# BEP2_rev1_multiCB.net
KiCad netlist of a schematic drawn in EAGLE
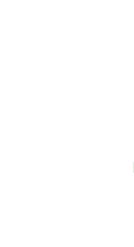
[diagram p0: schematic, sheet 1, part 1 of 2]
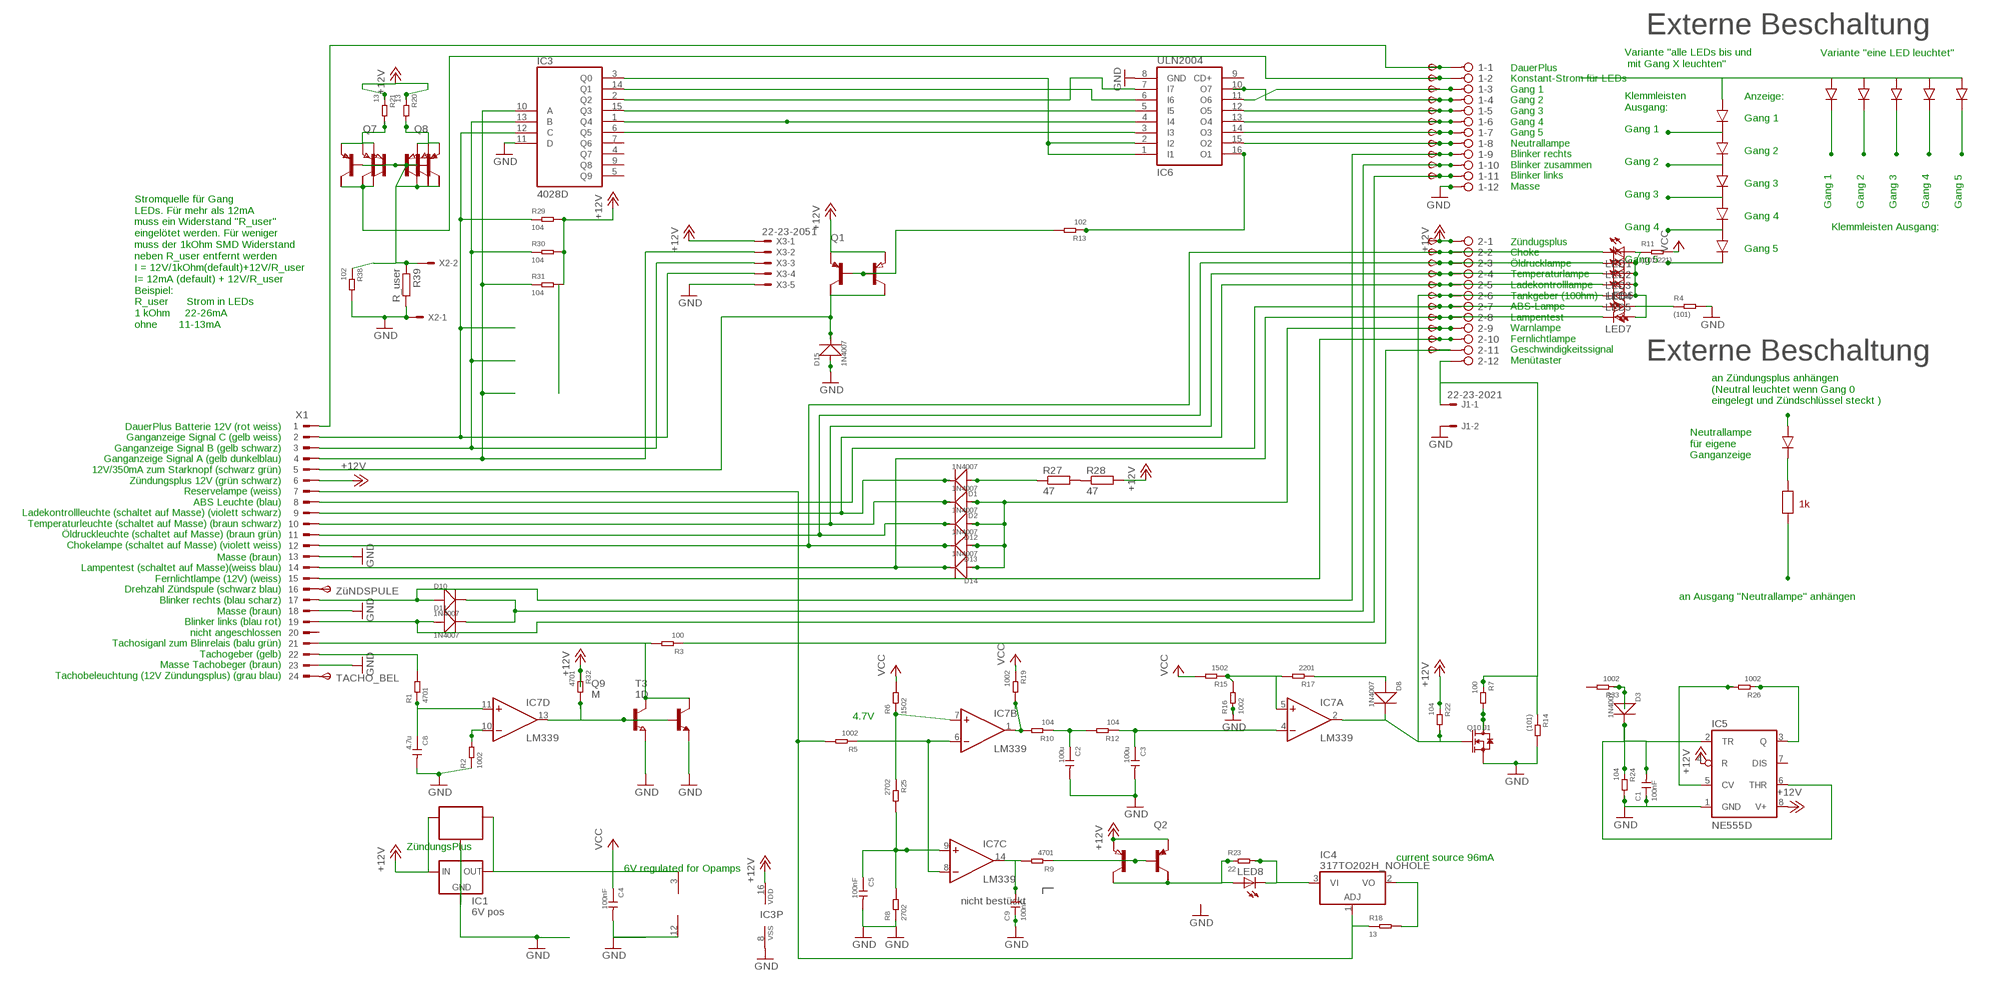
[diagram p1: schematic, sheet 1, part 2 of 2]

(export (version "E")
  (design (tool "Eeschema 10.0.6"))
  (components
    (comp (ref "1")
      (value "2081-1132")
      (footprint "eagle-import:12-PIN")
      (libsource (lib "eagle-import") (part "2081-1132"))
    )
    (comp (ref "2")
      (value "2081-1132")
      (footprint "eagle-import:12-PIN")
      (libsource (lib "eagle-import") (part "2081-1132"))
    )
    (comp (ref "C1")
      (value "100nF")
      (footprint "eagle-import:C0805")
      (fields (field (name "MPN") "CC0805KRX7R9BB104"))
      (libsource (lib "eagle-import") (part "CERAMIC-100NF-50V-10%-X7R(0805)"))
    )
    (comp (ref "C2")
      (value "100u")
      (footprint "eagle-import:C1206")
      (fields (field (name "MPN") "GRM31CR60J107ME39L"))
      (libsource (lib "eagle-import") (part "CERAMIC-100UF-6.3V-20%-X5R(1206)"))
    )
    (comp (ref "C3")
      (value "100u")
      (footprint "eagle-import:C1206")
      (fields (field (name "MPN") "GRM31CR60J107ME39L"))
      (libsource (lib "eagle-import") (part "CERAMIC-100UF-6.3V-20%-X5R(1206)"))
    )
    (comp (ref "C4")
      (value "100nF")
      (footprint "eagle-import:C0805")
      (fields (field (name "MPN") "CC0805KRX7R9BB104"))
      (libsource (lib "eagle-import") (part "CERAMIC-100NF-50V-10%-X7R(0805)"))
    )
    (comp (ref "C5")
      (value "100nF")
      (footprint "eagle-import:C0805")
      (fields (field (name "MPN") "CC0805KRX7R9BB104"))
      (libsource (lib "eagle-import") (part "CERAMIC-100NF-50V-10%-X7R(0805)"))
    )
    (comp (ref "C8")
      (value "4.7u")
      (footprint "eagle-import:C0805")
      (fields (field (name "MPN") "CC0805KKX5R8BB475"))
      (libsource (lib "eagle-import") (part "CERAMIC-4.7UF-25V-10%-X5R(0805)"))
    )
    (comp (ref "C9")
      (value "100nF")
      (footprint "eagle-import:C0805")
      (fields (field (name "MPN") "CC0805KRX7R9BB104"))
      (libsource (lib "eagle-import") (part "CERAMIC-100NF-50V-10%-X7R(0805)"))
    )
    (comp (ref "D1")
      (value "1N4007")
      (footprint "eagle-import:DO-214AC")
      (libsource (lib "eagle-import") (part "DIODE-GEN-PURPOSE-1KV-1A(DO-214AC)"))
    )
    (comp (ref "D2")
      (value "1N4007")
      (footprint "eagle-import:DO-214AC")
      (libsource (lib "eagle-import") (part "DIODE-GEN-PURPOSE-1KV-1A(DO-214AC)"))
    )
    (comp (ref "D3")
      (value "1N4007")
      (footprint "eagle-import:DO-214AC")
      (libsource (lib "eagle-import") (part "DIODE-GEN-PURPOSE-1KV-1A(DO-214AC)"))
    )
    (comp (ref "D8")
      (value "1N4007")
      (footprint "eagle-import:DO-214AC")
      (libsource (lib "eagle-import") (part "Seeed-Diode-2016_DIODE-GEN-PURPOSE-1KV-1A(DO-214AC)"))
    )
    (comp (ref "D10")
      (value "1N4007")
      (footprint "eagle-import:DO-214AC")
      (libsource (lib "eagle-import") (part "DIODE-GEN-PURPOSE-1KV-1A(DO-214AC)"))
    )
    (comp (ref "D11")
      (value "1N4007")
      (footprint "eagle-import:DO-214AC")
      (libsource (lib "eagle-import") (part "DIODE-GEN-PURPOSE-1KV-1A(DO-214AC)"))
    )
    (comp (ref "D12")
      (value "1N4007")
      (footprint "eagle-import:DO-214AC")
      (libsource (lib "eagle-import") (part "DIODE-GEN-PURPOSE-1KV-1A(DO-214AC)"))
    )
    (comp (ref "D13")
      (value "1N4007")
      (footprint "eagle-import:DO-214AC")
      (libsource (lib "eagle-import") (part "DIODE-GEN-PURPOSE-1KV-1A(DO-214AC)"))
    )
    (comp (ref "D14")
      (value "1N4007")
      (footprint "eagle-import:DO-214AC")
      (libsource (lib "eagle-import") (part "DIODE-GEN-PURPOSE-1KV-1A(DO-214AC)"))
    )
    (comp (ref "D15")
      (value "1N4007")
      (footprint "eagle-import:DO-214AC")
      (libsource (lib "eagle-import") (part "DIODE-GEN-PURPOSE-1KV-1A(DO-214AC)"))
    )
    (comp (ref "IC1")
      (value "6V pos")
      (footprint "eagle-import:78LXX")
      (libsource (lib "eagle-import") (part "v-reg_78LXX"))
    )
    (comp (ref "IC2")
      (value "78LXX-SOT89")
      (footprint "eagle-import:SOT89")
      (libsource (lib "eagle-import") (part "78LXX-SOT89"))
    )
    (comp (ref "IC3")
      (value "4028D")
      (footprint "eagle-import:SO16")
      (libsource (lib "eagle-import") (part "4028D"))
    )
    (comp (ref "IC4")
      (value "317TO202H_NOHOLE")
      (footprint "eagle-import:TO220H_NOHOLE")
      (libsource (lib "eagle-import") (part "317TO202H_NOHOLE"))
    )
    (comp (ref "IC5")
      (value "NE555D")
      (footprint "eagle-import:SO08")
      (libsource (lib "eagle-import") (part "555DNE"))
    )
    (comp (ref "IC6")
      (value "ULN2004")
      (footprint "eagle-import:SO16")
      (libsource (lib "eagle-import") (part "ULN2004AD"))
    )
    (comp (ref "IC7")
      (value "LM339")
      (footprint "eagle-import:SO14")
      (libsource (lib "eagle-import") (part "LM339D"))
    )
    (comp (ref "J1")
      (value "22-23-2021")
      (footprint "eagle-import:22-23-2021")
      (fields (field (name "MF") "MOLEX"))
      (libsource (lib "eagle-import") (part "22-23-2021"))
    )
    (comp (ref "LED1")
      (value "LEDLD260")
      (footprint "eagle-import:LD260")
      (libsource (lib "eagle-import") (part "LEDLD260"))
    )
    (comp (ref "LED2")
      (value "LEDLD260")
      (footprint "eagle-import:LD260")
      (libsource (lib "eagle-import") (part "LEDLD260"))
    )
    (comp (ref "LED3")
      (value "LEDLD260")
      (footprint "eagle-import:LD260")
      (libsource (lib "eagle-import") (part "LEDLD260"))
    )
    (comp (ref "LED4")
      (value "LEDLD260")
      (footprint "eagle-import:LD260")
      (libsource (lib "eagle-import") (part "LEDLD260"))
    )
    (comp (ref "LED5")
      (value "LEDLD260")
      (footprint "eagle-import:LD260")
      (libsource (lib "eagle-import") (part "LEDLD260"))
    )
    (comp (ref "LED6")
      (value "LEDLD260")
      (footprint "eagle-import:LD260")
      (libsource (lib "eagle-import") (part "LEDLD260"))
    )
    (comp (ref "LED7")
      (value "LEDLD260")
      (footprint "eagle-import:LD260")
      (libsource (lib "eagle-import") (part "LEDLD260"))
    )
    (comp (ref "LED8")
      (value "LEDLD260")
      (footprint "eagle-import:LD260")
      (libsource (lib "eagle-import") (part "LEDLD260"))
    )
    (comp (ref "Q1")
      (value "PNP-TRANSISTOR_SOT89")
      (footprint "eagle-import:SOT89")
      (libsource (lib "eagle-import") (part "PNP-TRANSISTOR_SOT89"))
    )
    (comp (ref "Q2")
      (value "PNP-TRANSISTOR_SOT89")
      (footprint "eagle-import:SOT89")
      (libsource (lib "eagle-import") (part "PNP-TRANSISTOR_SOT89"))
    )
    (comp (ref "Q3")
      (value "AH-16")
      (footprint "eagle-import:SOT223")
      (libsource (lib "eagle-import") (part "BCP53T1"))
    )
    (comp (ref "Q4")
      (value "AH-16")
      (footprint "eagle-import:SOT223")
      (libsource (lib "eagle-import") (part "BCP53T1"))
    )
    (comp (ref "Q5")
      (value "(AH-16)")
      (footprint "eagle-import:SOT223")
      (libsource (lib "eagle-import") (part "BCP53T1"))
    )
    (comp (ref "Q6")
      (value "(AH-16)")
      (footprint "eagle-import:SOT223")
      (libsource (lib "eagle-import") (part "BCP53T1"))
    )
    (comp (ref "Q7")
      (value "PNP-TRANSISTOR_SOT89")
      (footprint "eagle-import:SOT89")
      (libsource (lib "eagle-import") (part "PNP-TRANSISTOR_SOT89"))
    )
    (comp (ref "Q8")
      (value "PNP-TRANSISTOR_SOT89")
      (footprint "eagle-import:SOT89")
      (libsource (lib "eagle-import") (part "PNP-TRANSISTOR_SOT89"))
    )
    (comp (ref "Q9")
      (value "M")
      (footprint "eagle-import:SOT89")
      (libsource (lib "eagle-import") (part "NPN-TRANSISTOR_SOT89"))
    )
    (comp (ref "Q10")
      (value "J1")
      (footprint "eagle-import:SOT-23")
      (fields (field (name "MPN") "BSS138W-7-F"))
      (libsource (lib "eagle-import") (part "SMD-MOSFET-N-CH-50V-200MA-BSS138W-7-F(SOT-23)"))
    )
    (comp (ref "R1")
      (value "4701")
      (footprint "eagle-import:R0805")
      (fields (field (name "MPN") "RC0805JR-074K7L"))
      (libsource (lib "eagle-import") (part "SMD-RES-4.7K-5%-1/8W(0805)"))
    )
    (comp (ref "R2")
      (value "1002")
      (footprint "eagle-import:R0805")
      (fields (field (name "MPN") "RC0805FR-0710KL"))
      (libsource (lib "eagle-import") (part "SMD-RES-10K-1%-1/8W(0805)"))
    )
    (comp (ref "R3")
      (value "100")
      (footprint "eagle-import:R0805")
      (fields (field (name "MPN") "RC0805JR-07220RL"))
      (libsource (lib "eagle-import") (part "SMD-RES-220R-5%-1/8W(0805)"))
    )
    (comp (ref "R4")
      (value "(101)")
      (footprint "eagle-import:R0805")
      (fields (field (name "MPN") "RC0805JR-07100RL"))
      (libsource (lib "eagle-import") (part "SMD-RES-100R-5%-1/8W(0805)"))
    )
    (comp (ref "R5")
      (value "1002")
      (footprint "eagle-import:R0805")
      (fields (field (name "MPN") "RC0805FR-0710KL"))
      (libsource (lib "eagle-import") (part "SMD-RES-10K-1%-1/8W(0805)"))
    )
    (comp (ref "R6")
      (value "1502")
      (footprint "eagle-import:R0805")
      (fields (field (name "MPN") "RC0805FR-0710KL"))
      (libsource (lib "eagle-import") (part "SMD-RES-10K-1%-1/8W(0805)"))
    )
    (comp (ref "R7")
      (value "100")
      (footprint "eagle-import:R0805")
      (fields (field (name "MPN") "RC0805JR-072K2L"))
      (libsource (lib "eagle-import") (part "SMD-RES-2.2K-5%-1/8W(0805)"))
    )
    (comp (ref "R8")
      (value "2702")
      (footprint "eagle-import:R0805")
      (fields (field (name "MPN") "RC0805JR-074K7L"))
      (libsource (lib "eagle-import") (part "SMD-RES-4.7K-5%-1/8W(0805)"))
    )
    (comp (ref "R9")
      (value "4701")
      (footprint "eagle-import:R0805")
      (fields (field (name "MPN") "RC0805JR-074K7L"))
      (libsource (lib "eagle-import") (part "SMD-RES-4.7K-5%-1/8W(0805)"))
    )
    (comp (ref "R10")
      (value "104")
      (footprint "eagle-import:R0805")
      (fields (field (name "MPN") "RC0805FR-0710KL"))
      (libsource (lib "eagle-import") (part "SMD-RES-10K-1%-1/8W(0805)"))
    )
    (comp (ref "R11")
      (value "(101/221)")
      (footprint "eagle-import:R0805")
      (fields (field (name "MPN") "RC0805JR-07100RL"))
      (libsource (lib "eagle-import") (part "SMD-RES-100R-5%-1/8W(0805)"))
    )
    (comp (ref "R12")
      (value "104")
      (footprint "eagle-import:R0805")
      (fields (field (name "MPN") "RC0805FR-0710KL"))
      (libsource (lib "eagle-import") (part "SMD-RES-10K-1%-1/8W(0805)"))
    )
    (comp (ref "R13")
      (value "102")
      (footprint "eagle-import:R0805")
      (fields (field (name "MPN") "RC0805JR-071KL"))
      (libsource (lib "eagle-import") (part "SMD-RES-1K-5%-1/8W(0805)"))
    )
    (comp (ref "R14")
      (value "(101)")
      (footprint "eagle-import:R0805")
      (fields (field (name "MPN") "RC0805JR-072K2L"))
      (libsource (lib "eagle-import") (part "SMD-RES-2.2K-5%-1/8W(0805)"))
    )
    (comp (ref "R15")
      (value "1502")
      (footprint "eagle-import:R0805")
      (fields (field (name "MPN") "RC0805FR-0710KL"))
      (libsource (lib "eagle-import") (part "SMD-RES-10K-1%-1/8W(0805)"))
    )
    (comp (ref "R16")
      (value "1002")
      (footprint "eagle-import:R0805")
      (fields (field (name "MPN") "RC0805FR-0710KL"))
      (libsource (lib "eagle-import") (part "SMD-RES-10K-1%-1/8W(0805)"))
    )
    (comp (ref "R17")
      (value "2201")
      (footprint "eagle-import:R0805")
      (fields (field (name "MPN") "RC0805JR-072K2L"))
      (libsource (lib "eagle-import") (part "SMD-RES-2.2K-5%-1/8W(0805)"))
    )
    (comp (ref "R18")
      (value "13")
      (footprint "eagle-import:R1206")
      (fields (field (name "MPN") "RC1206JR-0713RL"))
      (libsource (lib "eagle-import") (part "SMD-RES-13R-5%-1/4W(1206)"))
    )
    (comp (ref "R19")
      (value "1002")
      (footprint "eagle-import:R0805")
      (fields (field (name "MPN") "RC0805FR-0710KL"))
      (libsource (lib "eagle-import") (part "SMD-RES-10K-1%-1/8W(0805)"))
    )
    (comp (ref "R20")
      (value "13")
      (footprint "eagle-import:R1206")
      (fields (field (name "MPN") "RC1206JR-0713RL"))
      (libsource (lib "eagle-import") (part "SMD-RES-13R-5%-1/4W(1206)"))
    )
    (comp (ref "R21")
      (value "13")
      (footprint "eagle-import:R1206")
      (fields (field (name "MPN") "RC1206JR-0713RL"))
      (libsource (lib "eagle-import") (part "SMD-RES-13R-5%-1/4W(1206)"))
    )
    (comp (ref "R22")
      (value "104")
      (footprint "eagle-import:R0805")
      (fields (field (name "MPN") "RC0805FR-0710KL"))
      (libsource (lib "eagle-import") (part "SMD-RES-10K-1%-1/8W(0805)"))
    )
    (comp (ref "R23")
      (value "22")
      (footprint "eagle-import:R1206")
      (fields (field (name "MPN") "RC1206JR-0713RL"))
      (libsource (lib "eagle-import") (part "SMD-RES-13R-5%-1/4W(1206)"))
    )
    (comp (ref "R24")
      (value "104")
      (footprint "eagle-import:R0805")
      (fields (field (name "MPN") "RC0805FR-0710KL"))
      (libsource (lib "eagle-import") (part "SMD-RES-10K-1%-1/8W(0805)"))
    )
    (comp (ref "R25")
      (value "2702")
      (footprint "eagle-import:R0805")
      (fields (field (name "MPN") "RC0805JR-074K7L"))
      (libsource (lib "eagle-import") (part "SMD-RES-4.7K-5%-1/8W(0805)"))
    )
    (comp (ref "R26")
      (value "1002")
      (footprint "eagle-import:R0805")
      (fields (field (name "MPN") "RC0805FR-0710KL"))
      (libsource (lib "eagle-import") (part "SMD-RES-10K-1%-1/8W(0805)"))
    )
    (comp (ref "R27")
      (value "47")
      (footprint "eagle-import:V235_17_1MM")
      (libsource (lib "eagle-import") (part "R-EU_V235/17_1MM"))
    )
    (comp (ref "R28")
      (value "47")
      (footprint "eagle-import:V235_17_1MM")
      (libsource (lib "eagle-import") (part "R-EU_V235/17_1MM"))
    )
    (comp (ref "R29")
      (value "104")
      (footprint "eagle-import:R0805")
      (fields (field (name "MPN") "RC0805FR-0710KL"))
      (libsource (lib "eagle-import") (part "SMD-RES-10K-1%-1/8W(0805)"))
    )
    (comp (ref "R30")
      (value "104")
      (footprint "eagle-import:R0805")
      (fields (field (name "MPN") "RC0805FR-0710KL"))
      (libsource (lib "eagle-import") (part "SMD-RES-10K-1%-1/8W(0805)"))
    )
    (comp (ref "R31")
      (value "104")
      (footprint "eagle-import:R0805")
      (fields (field (name "MPN") "RC0805FR-0710KL"))
      (libsource (lib "eagle-import") (part "SMD-RES-10K-1%-1/8W(0805)"))
    )
    (comp (ref "R32")
      (value "4701")
      (footprint "eagle-import:R0805")
      (fields (field (name "MPN") "RC0805JR-074K7L"))
      (libsource (lib "eagle-import") (part "SMD-RES-4.7K-5%-1/8W(0805)"))
    )
    (comp (ref "R33")
      (value "1002")
      (footprint "eagle-import:R0805")
      (fields (field (name "MPN") "RC0805FR-0710KL"))
      (libsource (lib "eagle-import") (part "SMD-RES-10K-1%-1/8W(0805)"))
    )
    (comp (ref "R38")
      (value "102")
      (footprint "eagle-import:R0805")
      (fields (field (name "MPN") "RC0805JR-071KL"))
      (libsource (lib "eagle-import") (part "SMD-RES-1K-5%-1/8W(0805)"))
    )
    (comp (ref "R39")
      (value "R_user")
      (footprint "eagle-import:R0805")
      (libsource (lib "eagle-import") (part "R-EU_R0805"))
    )
    (comp (ref "T1")
      (value "PNP2SM8")
      (footprint "eagle-import:SM8")
      (libsource (lib "eagle-import") (part "PNP2SM8"))
    )
    (comp (ref "T3")
      (value "1D")
      (footprint "eagle-import:SOT23-BEC")
      (libsource (lib "eagle-import") (part "-NPN-SOT23-BECMMBTA42LT1"))
    )
    (comp (ref "TACHO_BEL")
      (value "TPSP1_1MM")
      (footprint "eagle-import:P1_1.0MM")
      (libsource (lib "eagle-import") (part "TPSP1_1MM"))
    )
    (comp (ref "TP1")
      (value "TPSB1.8")
      (footprint "eagle-import:B1.8")
      (libsource (lib "eagle-import") (part "TPSB1.8"))
    )
    (comp (ref "TP2")
      (value "TPSB1.8")
      (footprint "eagle-import:B1.8")
      (libsource (lib "eagle-import") (part "TPSB1.8"))
    )
    (comp (ref "TP3")
      (value "TPSB1.8")
      (footprint "eagle-import:B1.8")
      (libsource (lib "eagle-import") (part "TPSB1.8"))
    )
    (comp (ref "TP4")
      (value "TPSB1.8")
      (footprint "eagle-import:B1.8")
      (libsource (lib "eagle-import") (part "TPSB1.8"))
    )
    (comp (ref "TP5")
      (value "TPSB1.8")
      (footprint "eagle-import:B1.8")
      (libsource (lib "eagle-import") (part "TPSB1.8"))
    )
    (comp (ref "TP6")
      (value "TPSB1.8")
      (footprint "eagle-import:B1.8")
      (libsource (lib "eagle-import") (part "TPSB1.8"))
    )
    (comp (ref "TP7")
      (value "TPSB1.8")
      (footprint "eagle-import:B1.8")
      (libsource (lib "eagle-import") (part "TPSB1.8"))
    )
    (comp (ref "TP8")
      (value "TPSB1.8")
      (footprint "eagle-import:B1.8")
      (libsource (lib "eagle-import") (part "TPSB1.8"))
    )
    (comp (ref "TP9")
      (value "TPSB1.8")
      (footprint "eagle-import:B1.8")
      (libsource (lib "eagle-import") (part "TPSB1.8"))
    )
    (comp (ref "TP10")
      (value "TPSB1.8")
      (footprint "eagle-import:B1.8")
      (libsource (lib "eagle-import") (part "TPSB1.8"))
    )
    (comp (ref "TP11")
      (value "TPSB1.8")
      (footprint "eagle-import:B1.8")
      (libsource (lib "eagle-import") (part "TPSB1.8"))
    )
    (comp (ref "TP12")
      (value "TPSB1.8")
      (footprint "eagle-import:B1.8")
      (libsource (lib "eagle-import") (part "TPSB1.8"))
    )
    (comp (ref "TP16")
      (value "TPSB1.8")
      (footprint "eagle-import:B1.8")
      (libsource (lib "eagle-import") (part "TPSB1.8"))
    )
    (comp (ref "TP17")
      (value "TPSB1.8")
      (footprint "eagle-import:B1.8")
      (libsource (lib "eagle-import") (part "TPSB1.8"))
    )
    (comp (ref "TP18")
      (value "TPSB1.8")
      (footprint "eagle-import:B1.8")
      (libsource (lib "eagle-import") (part "TPSB1.8"))
    )
    (comp (ref "TP19")
      (value "TPSB1.8")
      (footprint "eagle-import:B1.8")
      (libsource (lib "eagle-import") (part "TPSB1.8"))
    )
    (comp (ref "TP21")
      (value "TPSB1.8")
      (footprint "eagle-import:B1.8")
      (libsource (lib "eagle-import") (part "TPSB1.8"))
    )
    (comp (ref "TP22")
      (value "TPSB1.8")
      (footprint "eagle-import:B1.8")
      (libsource (lib "eagle-import") (part "TPSB1.8"))
    )
    (comp (ref "TP23")
      (value "TPSB1.8")
      (footprint "eagle-import:B1.8")
      (libsource (lib "eagle-import") (part "TPSB1.8"))
    )
    (comp (ref "TP24")
      (value "TPSB1,27")
      (footprint "eagle-import:B1,27")
      (libsource (lib "eagle-import") (part "TPSB1,27"))
    )
    (comp (ref "TP25")
      (value "TPSB1.8")
      (footprint "eagle-import:B1.8")
      (libsource (lib "eagle-import") (part "TPSB1.8"))
    )
    (comp (ref "TP26")
      (value "TPSB1.8")
      (footprint "eagle-import:B1.8")
      (libsource (lib "eagle-import") (part "TPSB1.8"))
    )
    (comp (ref "X1")
      (value "CON_BMWV2")
      (footprint "eagle-import:24-PIN_V2")
      (libsource (lib "eagle-import") (part "CON_BMWV2"))
    )
    (comp (ref "X2")
      (value "22-23-2021")
      (footprint "eagle-import:22-23-2021")
      (fields (field (name "MF") "MOLEX"))
      (libsource (lib "eagle-import") (part "22-23-2021"))
    )
    (comp (ref "X3")
      (value "22-23-2051")
      (footprint "eagle-import:22-23-2051")
      (fields (field (name "MF") "MOLEX"))
      (libsource (lib "eagle-import") (part "22-23-2051"))
    )
    (comp (ref "ZüNDSPULE")
      (value "TPSP1_1MM")
      (footprint "eagle-import:P1_1.0MM")
      (libsource (lib "eagle-import") (part "TPSP1_1MM"))
    )
  )
  (nets
    (net (code "1") (name "+12V") (class "Default")
      (node (ref "2") (pin "1") (pinfunction "KL_1") (pintype "passive"))
      (node (ref "IC1") (pin "IN") (pinfunction "IN_IN") (pintype "input"))
      (node (ref "IC2") (pin "3") (pinfunction "IN_3") (pintype "input"))
      (node (ref "IC3") (pin "16") (pinfunction "VDD_16") (pintype "power_in"))
      (node (ref "IC5") (pin "4") (pinfunction "R_4") (pintype "input"))
      (node (ref "IC5") (pin "8") (pinfunction "V+_8") (pintype "power_in"))
      (node (ref "Q1") (pin "3") (pinfunction "E_3") (pintype "passive"))
      (node (ref "Q2") (pin "3") (pinfunction "E_3") (pintype "passive"))
      (node (ref "Q3") (pin "3") (pinfunction "E_3") (pintype "passive"))
      (node (ref "Q4") (pin "3") (pinfunction "E_3") (pintype "passive"))
      (node (ref "R20") (pin "1") (pinfunction "1_1") (pintype "passive"))
      (node (ref "R21") (pin "1") (pinfunction "1_1") (pintype "passive"))
      (node (ref "R22") (pin "1") (pinfunction "1_1") (pintype "passive"))
      (node (ref "R28") (pin "2") (pinfunction "2_2") (pintype "passive"))
      (node (ref "R29") (pin "2") (pinfunction "2_2") (pintype "passive"))
      (node (ref "R30") (pin "2") (pinfunction "2_2") (pintype "passive"))
      (node (ref "R31") (pin "2") (pinfunction "2_2") (pintype "passive"))
      (node (ref "R32") (pin "1") (pinfunction "1_1") (pintype "passive"))
      (node (ref "TP12") (pin "TP") (pinfunction "PP_TP") (pintype "input"))
      (node (ref "X1") (pin "6") (pinfunction "6_6") (pintype "passive"))
      (node (ref "X3") (pin "1") (pinfunction "S_1") (pintype "passive"))
    )
    (net (code "2") (name "GND") (class "Default")
      (node (ref "1") (pin "12") (pinfunction "KL_12") (pintype "passive"))
      (node (ref "C1") (pin "1") (pinfunction "1_1") (pintype "passive"))
      (node (ref "C2") (pin "2") (pinfunction "2_2") (pintype "passive"))
      (node (ref "C3") (pin "2") (pinfunction "2_2") (pintype "passive"))
      (node (ref "C4") (pin "2") (pinfunction "2_2") (pintype "passive"))
      (node (ref "C5") (pin "2") (pinfunction "2_2") (pintype "passive"))
      (node (ref "C8") (pin "2") (pinfunction "2_2") (pintype "passive"))
      (node (ref "C9") (pin "1") (pinfunction "1_1") (pintype "passive"))
      (node (ref "D15") (pin "1") (pinfunction "+_1") (pintype "passive"))
      (node (ref "IC1") (pin "GND") (pinfunction "GND_GND") (pintype "input"))
      (node (ref "IC2") (pin "2") (pinfunction "GND_2") (pintype "input"))
      (node (ref "IC2") (pin "4") (pinfunction "GND_4") (pintype "input"))
      (node (ref "IC3") (pin "11") (pinfunction "D_11") (pintype "input"))
      (node (ref "IC3") (pin "8") (pinfunction "VSS_8") (pintype "power_in"))
      (node (ref "IC5") (pin "1") (pinfunction "GND_1") (pintype "power_in"))
      (node (ref "IC6") (pin "8") (pinfunction "GND_8") (pintype "power_in"))
      (node (ref "IC7") (pin "12") (pinfunction "GND_12") (pintype "power_in"))
      (node (ref "J1") (pin "2") (pinfunction "S_2") (pintype "passive"))
      (node (ref "Q10") (pin "2") (pinfunction "S_2") (pintype "passive"))
      (node (ref "Q9") (pin "3") (pinfunction "E_3") (pintype "passive"))
      (node (ref "R14") (pin "2") (pinfunction "2_2") (pintype "passive"))
      (node (ref "R16") (pin "1") (pinfunction "1_1") (pintype "passive"))
      (node (ref "R2") (pin "1") (pinfunction "1_1") (pintype "passive"))
      (node (ref "R24") (pin "2") (pinfunction "2_2") (pintype "passive"))
      (node (ref "R38") (pin "2") (pinfunction "2_2") (pintype "passive"))
      (node (ref "R39") (pin "2") (pinfunction "2_2") (pintype "passive"))
      (node (ref "R4") (pin "2") (pinfunction "2_2") (pintype "passive"))
      (node (ref "R8") (pin "1") (pinfunction "1_1") (pintype "passive"))
      (node (ref "T3") (pin "E") (pinfunction "E_E") (pintype "passive"))
      (node (ref "X1") (pin "13") (pinfunction "13_13") (pintype "passive"))
      (node (ref "X1") (pin "18") (pinfunction "18_18") (pintype "passive"))
      (node (ref "X1") (pin "23") (pinfunction "23_23") (pintype "passive"))
      (node (ref "X2") (pin "1") (pinfunction "S_1") (pintype "passive"))
      (node (ref "X3") (pin "5") (pinfunction "S_5") (pintype "passive"))
    )
    (net (code "3") (name "Net-(1A-KL)") (class "Default")
      (node (ref "1") (pin "1") (pinfunction "KL_1") (pintype "passive"))
      (node (ref "TP1") (pin "TP") (pinfunction "PP_TP") (pintype "input"))
      (node (ref "X1") (pin "1") (pinfunction "1_1") (pintype "passive"))
    )
    (net (code "4") (name "Net-(1B-KL)") (class "Default")
      (node (ref "1") (pin "10") (pinfunction "KL_10") (pintype "passive"))
      (node (ref "D10") (pin "2") (pinfunction "-_2") (pintype "passive"))
      (node (ref "D11") (pin "2") (pinfunction "-_2") (pintype "passive"))
      (node (ref "TP10") (pin "TP") (pinfunction "PP_TP") (pintype "input"))
    )
    (net (code "5") (name "Net-(1C-KL)") (class "Default")
      (node (ref "1") (pin "11") (pinfunction "KL_11") (pintype "passive"))
      (node (ref "D11") (pin "1") (pinfunction "+_1") (pintype "passive"))
      (node (ref "TP11") (pin "TP") (pinfunction "PP_TP") (pintype "input"))
      (node (ref "X1") (pin "19") (pinfunction "19_19") (pintype "passive"))
    )
    (net (code "6") (name "Net-(1E-KL)") (class "Default")
      (node (ref "1") (pin "2") (pinfunction "KL_2") (pintype "passive"))
      (node (ref "Q5") (pin "2") (pinfunction "C_2") (pintype "passive"))
      (node (ref "Q8") (pin "2") (pinfunction "C_2") (pintype "passive"))
      (node (ref "T1") (pin "8") (pinfunction "C1_8") (pintype "passive"))
      (node (ref "TP2") (pin "TP") (pinfunction "PP_TP") (pintype "input"))
    )
    (net (code "7") (name "Net-(1F-KL)") (class "Default")
      (node (ref "1") (pin "3") (pinfunction "KL_3") (pintype "passive"))
      (node (ref "IC6") (pin "11") (pinfunction "O6_11") (pintype "open_collector"))
      (node (ref "TP3") (pin "TP") (pinfunction "PP_TP") (pintype "input"))
    )
    (net (code "8") (name "Net-(1G-KL)") (class "Default")
      (node (ref "1") (pin "4") (pinfunction "KL_4") (pintype "passive"))
      (node (ref "IC6") (pin "10") (pinfunction "O7_10") (pintype "open_collector"))
      (node (ref "TP4") (pin "TP") (pinfunction "PP_TP") (pintype "input"))
    )
    (net (code "9") (name "Net-(1H-KL)") (class "Default")
      (node (ref "1") (pin "5") (pinfunction "KL_5") (pintype "passive"))
      (node (ref "IC6") (pin "12") (pinfunction "O5_12") (pintype "open_collector"))
      (node (ref "TP5") (pin "TP") (pinfunction "PP_TP") (pintype "input"))
    )
    (net (code "10") (name "Net-(1I-KL)") (class "Default")
      (node (ref "1") (pin "6") (pinfunction "KL_6") (pintype "passive"))
      (node (ref "IC6") (pin "13") (pinfunction "O4_13") (pintype "open_collector"))
      (node (ref "TP6") (pin "TP") (pinfunction "PP_TP") (pintype "input"))
    )
    (net (code "11") (name "Net-(1J-KL)") (class "Default")
      (node (ref "1") (pin "7") (pinfunction "KL_7") (pintype "passive"))
      (node (ref "IC6") (pin "14") (pinfunction "O3_14") (pintype "open_collector"))
      (node (ref "TP7") (pin "TP") (pinfunction "PP_TP") (pintype "input"))
    )
    (net (code "12") (name "Net-(1K-KL)") (class "Default")
      (node (ref "1") (pin "8") (pinfunction "KL_8") (pintype "passive"))
      (node (ref "IC6") (pin "15") (pinfunction "O2_15") (pintype "open_collector"))
      (node (ref "TP8") (pin "TP") (pinfunction "PP_TP") (pintype "input"))
    )
    (net (code "13") (name "Net-(1L-KL)") (class "Default")
      (node (ref "1") (pin "9") (pinfunction "KL_9") (pintype "passive"))
      (node (ref "D10") (pin "1") (pinfunction "+_1") (pintype "passive"))
      (node (ref "TP9") (pin "TP") (pinfunction "PP_TP") (pintype "input"))
      (node (ref "X1") (pin "17") (pinfunction "17_17") (pintype "passive"))
    )
    (net (code "14") (name "Net-(2B-KL)") (class "Default")
      (node (ref "2") (pin "10") (pinfunction "KL_10") (pintype "passive"))
      (node (ref "TP25") (pin "TP") (pinfunction "PP_TP") (pintype "input"))
      (node (ref "X1") (pin "15") (pinfunction "15_15") (pintype "passive"))
    )
    (net (code "15") (name "Net-(2C-KL)") (class "Default")
      (node (ref "2") (pin "11") (pinfunction "KL_11") (pintype "passive"))
      (node (ref "R3") (pin "1") (pinfunction "1_1") (pintype "passive"))
      (node (ref "TP26") (pin "TP") (pinfunction "PP_TP") (pintype "input"))
    )
    (net (code "16") (name "Net-(2D-KL)") (class "Default")
      (node (ref "2") (pin "12") (pinfunction "KL_12") (pintype "passive"))
      (node (ref "J1") (pin "1") (pinfunction "S_1") (pintype "passive"))
      (node (ref "R14") (pin "1") (pinfunction "1_1") (pintype "passive"))
      (node (ref "R7") (pin "1") (pinfunction "1_1") (pintype "passive"))
    )
    (net (code "17") (name "Net-(2E-KL)") (class "Default")
      (node (ref "2") (pin "2") (pinfunction "KL_2") (pintype "passive"))
      (node (ref "D13") (pin "2") (pinfunction "-_2") (pintype "passive"))
      (node (ref "LED1") (pin "K") (pinfunction "C_K") (pintype "passive"))
      (node (ref "TP16") (pin "TP") (pinfunction "PP_TP") (pintype "input"))
      (node (ref "X1") (pin "12") (pinfunction "12_12") (pintype "passive"))
    )
    (net (code "18") (name "Net-(2F-KL)") (class "Default")
      (node (ref "2") (pin "3") (pinfunction "KL_3") (pintype "passive"))
      (node (ref "D12") (pin "2") (pinfunction "-_2") (pintype "passive"))
      (node (ref "LED2") (pin "K") (pinfunction "C_K") (pintype "passive"))
      (node (ref "TP17") (pin "TP") (pinfunction "PP_TP") (pintype "input"))
      (node (ref "X1") (pin "11") (pinfunction "11_11") (pintype "passive"))
    )
    (net (code "19") (name "Net-(2G-KL)") (class "Default")
      (node (ref "2") (pin "4") (pinfunction "KL_4") (pintype "passive"))
      (node (ref "D2") (pin "2") (pinfunction "-_2") (pintype "passive"))
      (node (ref "LED3") (pin "K") (pinfunction "C_K") (pintype "passive"))
      (node (ref "TP18") (pin "TP") (pinfunction "PP_TP") (pintype "input"))
      (node (ref "X1") (pin "10") (pinfunction "10_10") (pintype "passive"))
    )
    (net (code "20") (name "Net-(2H-KL)") (class "Default")
      (node (ref "2") (pin "5") (pinfunction "KL_5") (pintype "passive"))
      (node (ref "D1") (pin "2") (pinfunction "-_2") (pintype "passive"))
      (node (ref "LED4") (pin "K") (pinfunction "C_K") (pintype "passive"))
      (node (ref "TP19") (pin "TP") (pinfunction "PP_TP") (pintype "input"))
      (node (ref "X1") (pin "9") (pinfunction "9_9") (pintype "passive"))
    )
    (net (code "21") (name "Net-(2I-KL)") (class "Default")
      (node (ref "2") (pin "6") (pinfunction "KL_6") (pintype "passive"))
      (node (ref "D8") (pin "2") (pinfunction "-_2") (pintype "passive"))
      (node (ref "IC7") (pin "2") (pinfunction "OUT_2") (pintype "open_collector"))
      (node (ref "LED5") (pin "K") (pinfunction "C_K") (pintype "passive"))
      (node (ref "Q10") (pin "1") (pinfunction "G_1") (pintype "passive"))
      (node (ref "R22") (pin "2") (pinfunction "2_2") (pintype "passive"))
      (node (ref "TP21") (pin "TP") (pinfunction "PP_TP") (pintype "input"))
    )
    (net (code "22") (name "Net-(2J-KL)") (class "Default")
      (node (ref "2") (pin "7") (pinfunction "KL_7") (pintype "passive"))
      (node (ref "LED6") (pin "A") (pinfunction "A_A") (pintype "passive"))
      (node (ref "TP22") (pin "TP") (pinfunction "PP_TP") (pintype "input"))
      (node (ref "X1") (pin "8") (pinfunction "8_8") (pintype "passive"))
    )
    (net (code "23") (name "Net-(2K-KL)") (class "Default")
      (node (ref "2") (pin "8") (pinfunction "KL_8") (pintype "passive"))
      (node (ref "D14") (pin "2") (pinfunction "-_2") (pintype "passive"))
      (node (ref "LED7") (pin "K") (pinfunction "C_K") (pintype "passive"))
      (node (ref "TP23") (pin "TP") (pinfunction "PP_TP") (pintype "input"))
      (node (ref "X1") (pin "14") (pinfunction "14_14") (pintype "passive"))
    )
    (net (code "24") (name "Net-(2L-KL)") (class "Default")
      (node (ref "2") (pin "9") (pinfunction "KL_9") (pintype "passive"))
      (node (ref "D12") (pin "1") (pinfunction "+_1") (pintype "passive"))
      (node (ref "D13") (pin "1") (pinfunction "+_1") (pintype "passive"))
      (node (ref "D14") (pin "1") (pinfunction "+_1") (pintype "passive"))
      (node (ref "D2") (pin "1") (pinfunction "+_1") (pintype "passive"))
      (node (ref "TP24") (pin "TP") (pinfunction "PP_TP") (pintype "input"))
    )
    (net (code "25") (name "Net-(C2-Pad1)") (class "Default")
      (node (ref "C2") (pin "1") (pinfunction "1_1") (pintype "passive"))
      (node (ref "R10") (pin "1") (pinfunction "1_1") (pintype "passive"))
      (node (ref "R12") (pin "2") (pinfunction "2_2") (pintype "passive"))
    )
    (net (code "26") (name "Net-(D1-+)") (class "Default")
      (node (ref "D1") (pin "1") (pinfunction "+_1") (pintype "passive"))
      (node (ref "R27") (pin "1") (pinfunction "1_1") (pintype "passive"))
    )
    (net (code "27") (name "Net-(D3-+)") (class "Default")
      (node (ref "D3") (pin "1") (pinfunction "+_1") (pintype "passive"))
      (node (ref "R33") (pin "1") (pinfunction "1_1") (pintype "passive"))
    )
    (net (code "28") (name "Net-(D3--)") (class "Default")
      (node (ref "C1") (pin "2") (pinfunction "2_2") (pintype "passive"))
      (node (ref "D3") (pin "2") (pinfunction "-_2") (pintype "passive"))
      (node (ref "IC5") (pin "2") (pinfunction "TR_2") (pintype "input"))
      (node (ref "IC5") (pin "6") (pinfunction "THR_6") (pintype "input"))
      (node (ref "R24") (pin "1") (pinfunction "1_1") (pintype "passive"))
    )
    (net (code "29") (name "Net-(D8-+)") (class "Default")
      (node (ref "D8") (pin "1") (pinfunction "+_1") (pintype "passive"))
      (node (ref "R17") (pin "1") (pinfunction "1_1") (pintype "passive"))
    )
    (net (code "30") (name "Net-(D15--)") (class "Default")
      (node (ref "D15") (pin "2") (pinfunction "-_2") (pintype "passive"))
      (node (ref "Q1") (pin "2") (pinfunction "C_2") (pintype "passive"))
      (node (ref "Q3") (pin "2") (pinfunction "C_2") (pintype "passive"))
      (node (ref "X1") (pin "5") (pinfunction "5_5") (pintype "passive"))
    )
    (net (code "31") (name "Net-(IC3A-A)") (class "Default")
      (node (ref "IC3") (pin "10") (pinfunction "A_10") (pintype "input"))
      (node (ref "R31") (pin "1") (pinfunction "1_1") (pintype "passive"))
      (node (ref "X1") (pin "4") (pinfunction "4_4") (pintype "passive"))
      (node (ref "X3") (pin "2") (pinfunction "S_2") (pintype "passive"))
    )
    (net (code "32") (name "Net-(IC3A-B)") (class "Default")
      (node (ref "IC3") (pin "13") (pinfunction "B_13") (pintype "input"))
      (node (ref "R30") (pin "1") (pinfunction "1_1") (pintype "passive"))
      (node (ref "X1") (pin "3") (pinfunction "3_3") (pintype "passive"))
      (node (ref "X3") (pin "3") (pinfunction "S_3") (pintype "passive"))
    )
    (net (code "33") (name "Net-(IC3A-C)") (class "Default")
      (node (ref "IC3") (pin "12") (pinfunction "C_12") (pintype "input"))
      (node (ref "R29") (pin "1") (pinfunction "1_1") (pintype "passive"))
      (node (ref "X1") (pin "2") (pinfunction "2_2") (pintype "passive"))
      (node (ref "X3") (pin "4") (pinfunction "S_4") (pintype "passive"))
    )
    (net (code "34") (name "Net-(IC3A-Q0)") (class "Default")
      (node (ref "IC3") (pin "3") (pinfunction "Q0_3") (pintype "output"))
      (node (ref "IC6") (pin "1") (pinfunction "I1_1") (pintype "input"))
      (node (ref "IC6") (pin "2") (pinfunction "I2_2") (pintype "input"))
    )
    (net (code "35") (name "Net-(IC3A-Q1)") (class "Default")
      (node (ref "IC3") (pin "14") (pinfunction "Q1_14") (pintype "output"))
      (node (ref "IC6") (pin "6") (pinfunction "I6_6") (pintype "input"))
    )
    (net (code "36") (name "Net-(IC3A-Q2)") (class "Default")
      (node (ref "IC3") (pin "2") (pinfunction "Q2_2") (pintype "output"))
      (node (ref "IC6") (pin "7") (pinfunction "I7_7") (pintype "input"))
    )
    (net (code "37") (name "Net-(IC3A-Q3)") (class "Default")
      (node (ref "IC3") (pin "15") (pinfunction "Q3_15") (pintype "output"))
      (node (ref "IC6") (pin "5") (pinfunction "I5_5") (pintype "input"))
    )
    (net (code "38") (name "Net-(IC3A-Q4)") (class "Default")
      (node (ref "IC3") (pin "1") (pinfunction "Q4_1") (pintype "output"))
      (node (ref "IC6") (pin "4") (pinfunction "I4_4") (pintype "input"))
    )
    (net (code "39") (name "Net-(IC3A-Q5)") (class "Default")
      (node (ref "IC3") (pin "6") (pinfunction "Q5_6") (pintype "output"))
      (node (ref "IC6") (pin "3") (pinfunction "I3_3") (pintype "input"))
    )
    (net (code "40") (name "Net-(IC4-ADJ)") (class "Default")
      (node (ref "IC4") (pin "1") (pinfunction "ADJ_1") (pintype "input"))
      (node (ref "R18") (pin "1") (pinfunction "1_1") (pintype "passive"))
      (node (ref "R5") (pin "2") (pinfunction "2_2") (pintype "passive"))
      (node (ref "X1") (pin "7") (pinfunction "7_7") (pintype "passive"))
    )
    (net (code "41") (name "Net-(IC4-VI)") (class "Default")
      (node (ref "IC4") (pin "3") (pinfunction "VI_3") (pintype "input"))
      (node (ref "LED8") (pin "K") (pinfunction "C_K") (pintype "passive"))
      (node (ref "R23") (pin "2") (pinfunction "2_2") (pintype "passive"))
    )
    (net (code "42") (name "Net-(IC4-VO)") (class "Default")
      (node (ref "IC4") (pin "2") (pinfunction "VO_2") (pintype "passive"))
      (node (ref "R18") (pin "2") (pinfunction "2_2") (pintype "passive"))
    )
    (net (code "43") (name "Net-(IC5-CV)") (class "Default")
      (node (ref "IC5") (pin "5") (pinfunction "CV_5") (pintype "input"))
      (node (ref "R26") (pin "2") (pinfunction "2_2") (pintype "passive"))
    )
    (net (code "44") (name "Net-(IC5-Q)") (class "Default")
      (node (ref "IC5") (pin "3") (pinfunction "Q_3") (pintype "output"))
      (node (ref "R26") (pin "1") (pinfunction "1_1") (pintype "passive"))
    )
    (net (code "45") (name "Net-(IC6-O1)") (class "Default")
      (node (ref "IC6") (pin "16") (pinfunction "O1_16") (pintype "open_collector"))
      (node (ref "R13") (pin "1") (pinfunction "1_1") (pintype "passive"))
    )
    (net (code "46") (name "Net-(IC7A-+IN)") (class "Default")
      (node (ref "IC7") (pin "5") (pinfunction "+IN_5") (pintype "input"))
      (node (ref "R15") (pin "1") (pinfunction "1_1") (pintype "passive"))
      (node (ref "R16") (pin "2") (pinfunction "2_2") (pintype "passive"))
      (node (ref "R17") (pin "2") (pinfunction "2_2") (pintype "passive"))
    )
    (net (code "47") (name "Net-(IC7A--IN)") (class "Default")
      (node (ref "C3") (pin "1") (pinfunction "1_1") (pintype "passive"))
      (node (ref "IC7") (pin "4") (pinfunction "-IN_4") (pintype "input"))
      (node (ref "R12") (pin "1") (pinfunction "1_1") (pintype "passive"))
    )
    (net (code "48") (name "Net-(IC7B-+IN)") (class "Default")
      (node (ref "IC7") (pin "7") (pinfunction "+IN_7") (pintype "input"))
      (node (ref "R25") (pin "1") (pinfunction "1_1") (pintype "passive"))
      (node (ref "R6") (pin "1") (pinfunction "1_1") (pintype "passive"))
    )
    (net (code "49") (name "Net-(IC7B--IN)") (class "Default")
      (node (ref "IC7") (pin "6") (pinfunction "-IN_6") (pintype "input"))
      (node (ref "IC7") (pin "8") (pinfunction "-IN_8") (pintype "input"))
      (node (ref "R5") (pin "1") (pinfunction "1_1") (pintype "passive"))
    )
    (net (code "50") (name "Net-(IC7B-OUT)") (class "Default")
      (node (ref "IC7") (pin "1") (pinfunction "OUT_1") (pintype "open_collector"))
      (node (ref "R10") (pin "2") (pinfunction "2_2") (pintype "passive"))
      (node (ref "R19") (pin "2") (pinfunction "2_2") (pintype "passive"))
    )
    (net (code "51") (name "Net-(IC7C-+IN)") (class "Default")
      (node (ref "C5") (pin "1") (pinfunction "1_1") (pintype "passive"))
      (node (ref "IC7") (pin "9") (pinfunction "+IN_9") (pintype "input"))
      (node (ref "R25") (pin "2") (pinfunction "2_2") (pintype "passive"))
      (node (ref "R8") (pin "2") (pinfunction "2_2") (pintype "passive"))
    )
    (net (code "52") (name "Net-(IC7C-OUT)") (class "Default")
      (node (ref "C9") (pin "2") (pinfunction "2_2") (pintype "passive"))
      (node (ref "IC7") (pin "14") (pinfunction "OUT_14") (pintype "open_collector"))
      (node (ref "R9") (pin "2") (pinfunction "2_2") (pintype "passive"))
    )
    (net (code "53") (name "Net-(IC7D-+IN)") (class "Default")
      (node (ref "C8") (pin "1") (pinfunction "1_1") (pintype "passive"))
      (node (ref "IC7") (pin "11") (pinfunction "+IN_11") (pintype "input"))
      (node (ref "R1") (pin "1") (pinfunction "1_1") (pintype "passive"))
    )
    (net (code "54") (name "Net-(IC7D--IN)") (class "Default")
      (node (ref "IC7") (pin "10") (pinfunction "-IN_10") (pintype "input"))
      (node (ref "R2") (pin "2") (pinfunction "2_2") (pintype "passive"))
    )
    (net (code "55") (name "Net-(IC7D-OUT)") (class "Default")
      (node (ref "IC7") (pin "13") (pinfunction "OUT_13") (pintype "open_collector"))
      (node (ref "Q9") (pin "1") (pinfunction "B_1") (pintype "passive"))
      (node (ref "R32") (pin "2") (pinfunction "2_2") (pintype "passive"))
      (node (ref "T3") (pin "B") (pinfunction "B_B") (pintype "passive"))
    )
    (net (code "56") (name "Net-(LED1-PadA)") (class "Default")
      (node (ref "LED1") (pin "A") (pinfunction "A_A") (pintype "passive"))
      (node (ref "LED2") (pin "A") (pinfunction "A_A") (pintype "passive"))
      (node (ref "LED3") (pin "A") (pinfunction "A_A") (pintype "passive"))
      (node (ref "LED4") (pin "A") (pinfunction "A_A") (pintype "passive"))
      (node (ref "LED5") (pin "A") (pinfunction "A_A") (pintype "passive"))
      (node (ref "LED7") (pin "A") (pinfunction "A_A") (pintype "passive"))
      (node (ref "R11") (pin "1") (pinfunction "1_1") (pintype "passive"))
    )
    (net (code "57") (name "Net-(LED6-C)") (class "Default")
      (node (ref "LED6") (pin "K") (pinfunction "C_K") (pintype "passive"))
      (node (ref "R4") (pin "1") (pinfunction "1_1") (pintype "passive"))
    )
    (net (code "58") (name "Net-(Q1-B)") (class "Default")
      (node (ref "Q1") (pin "1") (pinfunction "B_1") (pintype "passive"))
      (node (ref "Q3") (pin "1") (pinfunction "B_1") (pintype "passive"))
      (node (ref "R13") (pin "2") (pinfunction "2_2") (pintype "passive"))
    )
    (net (code "59") (name "Net-(Q2-B)") (class "Default")
      (node (ref "Q2") (pin "1") (pinfunction "B_1") (pintype "passive"))
      (node (ref "Q4") (pin "1") (pinfunction "B_1") (pintype "passive"))
      (node (ref "R9") (pin "1") (pinfunction "1_1") (pintype "passive"))
    )
    (net (code "60") (name "Net-(Q2-C)") (class "Default")
      (node (ref "LED8") (pin "A") (pinfunction "A_A") (pintype "passive"))
      (node (ref "Q2") (pin "2") (pinfunction "C_2") (pintype "passive"))
      (node (ref "Q4") (pin "2") (pinfunction "C_2") (pintype "passive"))
      (node (ref "R23") (pin "1") (pinfunction "1_1") (pintype "passive"))
    )
    (net (code "61") (name "Net-(Q5-B)") (class "Default")
      (node (ref "Q5") (pin "1") (pinfunction "B_1") (pintype "passive"))
      (node (ref "Q6") (pin "1") (pinfunction "B_1") (pintype "passive"))
      (node (ref "Q6") (pin "2") (pinfunction "C_2") (pintype "passive"))
      (node (ref "Q7") (pin "1") (pinfunction "B_1") (pintype "passive"))
      (node (ref "Q7") (pin "2") (pinfunction "C_2") (pintype "passive"))
      (node (ref "Q8") (pin "1") (pinfunction "B_1") (pintype "passive"))
      (node (ref "R38") (pin "1") (pinfunction "1_1") (pintype "passive"))
      (node (ref "R39") (pin "1") (pinfunction "1_1") (pintype "passive"))
      (node (ref "T1") (pin "2") (pinfunction "B_2") (pintype "passive"))
      (node (ref "T1") (pin "4") (pinfunction "B_4") (pintype "passive"))
      (node (ref "T1") (pin "6") (pinfunction "C1_6") (pintype "passive"))
      (node (ref "X2") (pin "2") (pinfunction "S_2") (pintype "passive"))
    )
    (net (code "62") (name "Net-(Q5-E)") (class "Default")
      (node (ref "Q5") (pin "3") (pinfunction "E_3") (pintype "passive"))
      (node (ref "Q8") (pin "3") (pinfunction "E_3") (pintype "passive"))
      (node (ref "R21") (pin "2") (pinfunction "2_2") (pintype "passive"))
      (node (ref "T1") (pin "1") (pinfunction "E_1") (pintype "passive"))
    )
    (net (code "63") (name "Net-(Q6-E)") (class "Default")
      (node (ref "Q6") (pin "3") (pinfunction "E_3") (pintype "passive"))
      (node (ref "Q7") (pin "3") (pinfunction "E_3") (pintype "passive"))
      (node (ref "R20") (pin "2") (pinfunction "2_2") (pintype "passive"))
      (node (ref "T1") (pin "3") (pinfunction "E_3") (pintype "passive"))
    )
    (net (code "64") (name "Net-(Q9-C)") (class "Default")
      (node (ref "Q9") (pin "2") (pinfunction "C_2") (pintype "passive"))
      (node (ref "R3") (pin "2") (pinfunction "2_2") (pintype "passive"))
      (node (ref "T3") (pin "C") (pinfunction "C_C") (pintype "passive"))
      (node (ref "X1") (pin "21") (pinfunction "21_21") (pintype "passive"))
    )
    (net (code "65") (name "Net-(Q10-D)") (class "Default")
      (node (ref "Q10") (pin "3") (pinfunction "D_3") (pintype "passive"))
      (node (ref "R7") (pin "2") (pinfunction "2_2") (pintype "passive"))
    )
    (net (code "66") (name "Net-(R1-Pad2)") (class "Default")
      (node (ref "R1") (pin "2") (pinfunction "2_2") (pintype "passive"))
      (node (ref "X1") (pin "22") (pinfunction "22_22") (pintype "passive"))
    )
    (net (code "67") (name "Net-(R27-Pad2)") (class "Default")
      (node (ref "R27") (pin "2") (pinfunction "2_2") (pintype "passive"))
      (node (ref "R28") (pin "1") (pinfunction "1_1") (pintype "passive"))
    )
    (net (code "68") (name "Net-(TACHO_BEL-PP)") (class "Default")
      (node (ref "TACHO_BEL") (pin "TP") (pinfunction "PP_TP") (pintype "input"))
      (node (ref "X1") (pin "24") (pinfunction "24_24") (pintype "passive"))
    )
    (net (code "69") (name "Net-(ZüNDSPULE-PP)") (class "Default")
      (node (ref "X1") (pin "16") (pinfunction "16_16") (pintype "passive"))
      (node (ref "ZüNDSPULE") (pin "TP") (pinfunction "PP_TP") (pintype "input"))
    )
    (net (code "70") (name "VCC") (class "Default")
      (node (ref "C4") (pin "1") (pinfunction "1_1") (pintype "passive"))
      (node (ref "IC1") (pin "OUT") (pinfunction "OUT_OUT") (pintype "passive"))
      (node (ref "IC2") (pin "1") (pinfunction "OUT_1") (pintype "passive"))
      (node (ref "IC7") (pin "3") (pinfunction "V+_3") (pintype "power_in"))
      (node (ref "R11") (pin "2") (pinfunction "2_2") (pintype "passive"))
      (node (ref "R15") (pin "2") (pinfunction "2_2") (pintype "passive"))
      (node (ref "R19") (pin "1") (pinfunction "1_1") (pintype "passive"))
      (node (ref "R6") (pin "2") (pinfunction "2_2") (pintype "passive"))
    )
    (net (code "71") (name "unconnected-(IC3A-Q6-Pad7)") (class "Default")
      (node (ref "IC3") (pin "7") (pinfunction "Q6_7") (pintype "output"))
    )
    (net (code "72") (name "unconnected-(IC3A-Q7-Pad4)") (class "Default")
      (node (ref "IC3") (pin "4") (pinfunction "Q7_4") (pintype "output"))
    )
    (net (code "73") (name "unconnected-(IC3A-Q8-Pad9)") (class "Default")
      (node (ref "IC3") (pin "9") (pinfunction "Q8_9") (pintype "output"))
    )
    (net (code "74") (name "unconnected-(IC3A-Q9-Pad5)") (class "Default")
      (node (ref "IC3") (pin "5") (pinfunction "Q9_5") (pintype "output"))
    )
    (net (code "75") (name "unconnected-(IC5-DIS-Pad7)") (class "Default")
      (node (ref "IC5") (pin "7") (pinfunction "DIS_7") (pintype "input"))
    )
    (net (code "76") (name "unconnected-(IC6-CD+-Pad9)") (class "Default")
      (node (ref "IC6") (pin "9") (pinfunction "CD+_9") (pintype "passive"))
    )
    (net (code "77") (name "unconnected-(Q3-C{slash}-Pad4)") (class "Default")
      (node (ref "Q3") (pin "4") (pinfunction "C/_4") (pintype "passive"))
    )
    (net (code "78") (name "unconnected-(Q4-C{slash}-Pad4)") (class "Default")
      (node (ref "Q4") (pin "4") (pinfunction "C/_4") (pintype "passive"))
    )
    (net (code "79") (name "unconnected-(Q5-C{slash}-Pad4)") (class "Default")
      (node (ref "Q5") (pin "4") (pinfunction "C/_4") (pintype "passive"))
    )
    (net (code "80") (name "unconnected-(Q6-C{slash}-Pad4)") (class "Default")
      (node (ref "Q6") (pin "4") (pinfunction "C/_4") (pintype "passive"))
    )
    (net (code "81") (name "unconnected-(R33-Pad2)") (class "Default")
      (node (ref "R33") (pin "2") (pinfunction "2_2") (pintype "passive"))
    )
    (net (code "82") (name "unconnected-(T1A-C-Pad5)") (class "Default")
      (node (ref "T1") (pin "5") (pinfunction "C_5") (pintype "passive"))
    )
    (net (code "83") (name "unconnected-(T1B-C-Pad7)") (class "Default")
      (node (ref "T1") (pin "7") (pinfunction "C_7") (pintype "passive"))
    )
    (net (code "84") (name "unconnected-(X1-Pad20)") (class "Default")
      (node (ref "X1") (pin "20") (pinfunction "20_20") (pintype "passive"))
    )
  )
)
